# 2016_CARTE_PUISSANCEtemp.net
KiCad netlist of a schematic drawn in Altium Designer
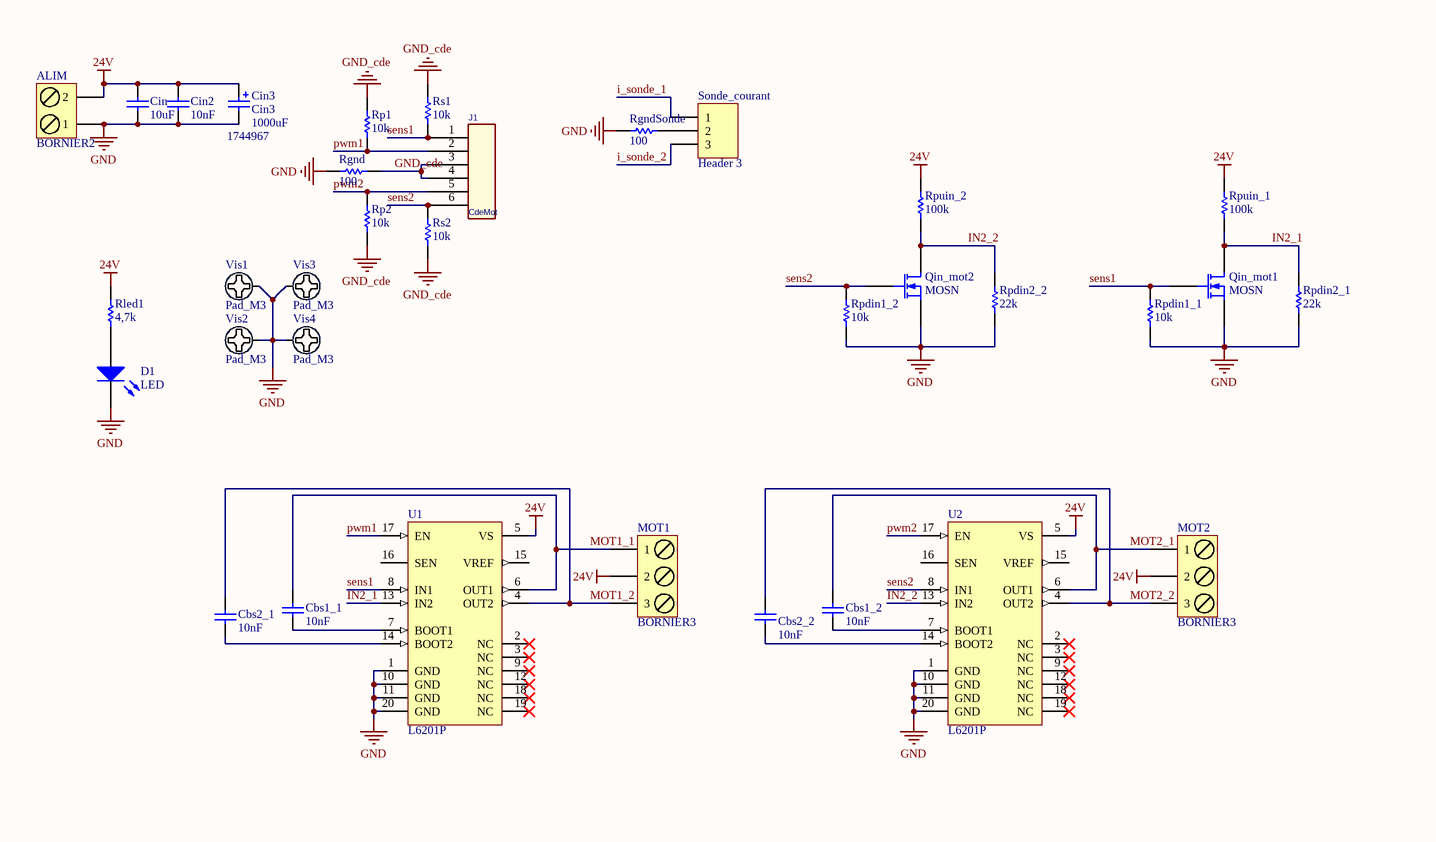
[diagram p0: 2016_CARTE_PUISSANCEtemp.SchDoc, left]
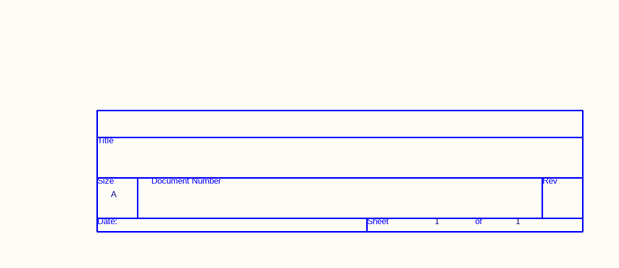
[diagram p1: 2016_CARTE_PUISSANCEtemp.SchDoc, right]

(export (version "E")
  (design (tool "Eeschema 10.0.6"))
  (components
    (comp (ref "*")
      (value "TitleBlock0")
      (fields (field (name "PAGE COUNT") "1") (field (name "PAGE NUMBER") "1") (field (name "PAGE SIZE") "A"))
      (libsource (lib "*") (part "TitleBlock0"))
    )
    (comp (ref "ALIM")
      (value "BORNIER2")
      (footprint "BORNIER2")
      (description "Terminal blocks, 2 pins, pitch=5mm")
      (libsource (lib "Robot2010") (part "BORNIER2"))
    )
    (comp (ref "Cbs1_1")
      (value "10nF")
      (footprint "C0805_N")
      (description "Capacitor")
      (fields (field (name "PUBLISHER") "Altium Limited"))
      (libsource (lib "DG_Condensateur") (part "Capacitor"))
    )
    (comp (ref "Cbs1_2")
      (value "10nF")
      (footprint "C0805_N")
      (description "Capacitor")
      (fields (field (name "PUBLISHER") "Altium Limited"))
      (libsource (lib "DG_Condensateur") (part "Capacitor"))
    )
    (comp (ref "Cbs2_1")
      (value "10nF")
      (footprint "C0805_N")
      (description "Capacitor")
      (fields (field (name "PUBLISHER") "Altium Limited"))
      (libsource (lib "DG_Condensateur") (part "Capacitor"))
    )
    (comp (ref "Cbs2_2")
      (value "10nF")
      (footprint "C0805_N")
      (description "Capacitor")
      (fields (field (name "PUBLISHER") "Altium Limited"))
      (libsource (lib "DG_Condensateur") (part "Capacitor"))
    )
    (comp (ref "Cin")
      (value "10uF")
      (footprint "C1206_N")
      (description "Capacitor")
      (fields (field (name "PUBLISHER") "Altium Limited"))
      (libsource (lib "DG_Condensateur") (part "Capacitor"))
    )
    (comp (ref "Cin2")
      (value "10nF")
      (footprint "C0805_N")
      (description "Capacitor")
      (fields (field (name "PUBLISHER") "Altium Limited"))
      (libsource (lib "DG_Condensateur") (part "Capacitor"))
    )
    (comp (ref "Cin3")
      (value "Cin3")
      (footprint "COND_POL_RAD_5.08B")
      (description "Polarized Capacitor")
      (fields
        (field (name "ALTIUM_VALUE") "1000uF")
        (field (name "FAR") "1744967")
        (field (name "PUBLISHER") "Altium Limited")
      )
      (libsource (lib "Robot2010") (part "CONDENSATEUR_POLARISE"))
    )
    (comp (ref "D1")
      (value "LED")
      (footprint "LED_3mm")
      (description "Typical LED")
      (fields (field (name "PUBLISHER") "Altium Limited"))
      (libsource (lib "DG_LED") (part "LED"))
    )
    (comp (ref "J1") (value "CdeMot") (footprint "RJ11_6/6") (libsource (lib "*") (part "CONNECTEUR_RJ12")))
    (comp (ref "MOT1")
      (value "BORNIER3")
      (footprint "BORNIER3")
      (description "Terminal blocks, 2 pins, pitch=5mm")
      (libsource (lib "Robot2010") (part "BORNIER3"))
    )
    (comp (ref "MOT2")
      (value "BORNIER3")
      (footprint "BORNIER3")
      (description "Terminal blocks, 2 pins, pitch=5mm")
      (libsource (lib "Robot2010") (part "BORNIER3"))
    )
    (comp (ref "Qin_mot1")
      (value "MOSN")
      (footprint "SOT23-3N")
      (description "N-Channel MOSFET")
      (fields (field (name "PUBLISHER") "Altium Limited"))
      (libsource (lib "_ROBOT") (part "Transistor MOSFET-N"))
    )
    (comp (ref "Qin_mot2")
      (value "MOSN")
      (footprint "SOT23-3N")
      (description "N-Channel MOSFET")
      (fields (field (name "PUBLISHER") "Altium Limited"))
      (libsource (lib "_ROBOT") (part "Transistor MOSFET-N"))
    )
    (comp (ref "Rgnd")
      (value "100")
      (footprint "R1206_N")
      (description "Resistor")
      (fields (field (name "PUBLISHER") "Altium Limited"))
      (libsource (lib "DG_Resistance") (part "Resistor"))
    )
    (comp (ref "RgndSonde")
      (value "100")
      (footprint "R1206_N")
      (description "Resistor")
      (fields (field (name "PUBLISHER") "Altium Limited"))
      (libsource (lib "DG_Resistance") (part "Resistor"))
    )
    (comp (ref "Rled1")
      (value "4,7k")
      (footprint "R1206_N")
      (description "Resistor")
      (fields (field (name "PUBLISHER") "Altium Limited"))
      (libsource (lib "DG_Resistance") (part "Resistor"))
    )
    (comp (ref "Rp1")
      (value "10k")
      (footprint "R1206_N")
      (description "Resistor")
      (fields (field (name "PUBLISHER") "Altium Limited"))
      (libsource (lib "DG_Resistance") (part "Resistor"))
    )
    (comp (ref "Rp2")
      (value "10k")
      (footprint "R1206_N")
      (description "Resistor")
      (fields (field (name "PUBLISHER") "Altium Limited"))
      (libsource (lib "DG_Resistance") (part "Resistor"))
    )
    (comp (ref "Rpdin1_1")
      (value "10k")
      (footprint "R1206_N")
      (description "Resistor")
      (fields (field (name "PUBLISHER") "Altium Limited"))
      (libsource (lib "DG_Resistance") (part "Resistor"))
    )
    (comp (ref "Rpdin1_2")
      (value "10k")
      (footprint "R1206_N")
      (description "Resistor")
      (fields (field (name "PUBLISHER") "Altium Limited"))
      (libsource (lib "DG_Resistance") (part "Resistor"))
    )
    (comp (ref "Rpdin2_1")
      (value "22k")
      (footprint "R1206_N")
      (description "Resistor")
      (fields (field (name "PUBLISHER") "Altium Limited"))
      (libsource (lib "DG_Resistance") (part "Resistor"))
    )
    (comp (ref "Rpdin2_2")
      (value "22k")
      (footprint "R1206_N")
      (description "Resistor")
      (fields (field (name "PUBLISHER") "Altium Limited"))
      (libsource (lib "DG_Resistance") (part "Resistor"))
    )
    (comp (ref "Rpuin_1")
      (value "100k")
      (footprint "R1206_N")
      (description "Resistor")
      (fields (field (name "PUBLISHER") "Altium Limited"))
      (libsource (lib "DG_Resistance") (part "Resistor"))
    )
    (comp (ref "Rpuin_2")
      (value "100k")
      (footprint "R1206_N")
      (description "Resistor")
      (fields (field (name "PUBLISHER") "Altium Limited"))
      (libsource (lib "DG_Resistance") (part "Resistor"))
    )
    (comp (ref "Rs1")
      (value "10k")
      (footprint "R1206_N")
      (description "Resistor")
      (fields (field (name "PUBLISHER") "Altium Limited"))
      (libsource (lib "DG_Resistance") (part "Resistor"))
    )
    (comp (ref "Rs2")
      (value "10k")
      (footprint "R1206_N")
      (description "Resistor")
      (fields (field (name "PUBLISHER") "Altium Limited"))
      (libsource (lib "DG_Resistance") (part "Resistor"))
    )
    (comp (ref "Sonde_courant")
      (value "Header 3")
      (footprint "HDR1X3")
      (description "Header, 3-Pin")
      (fields (field (name "PUBLISHER") "Altium Limited"))
      (libsource (lib "DG_Connecteur") (part "Header 3"))
    )
    (comp (ref "U1")
      (value "L6201P")
      (footprint "PowerSO20_N")
      (description "DMOS Full Bridge Driver")
      (fields (field (name "PUBLISHER") "Altium Limited"))
      (libsource (lib "ST Interface DC Motor Controller") (part "L6201P"))
    )
    (comp (ref "U2")
      (value "L6201P")
      (footprint "PowerSO20_N")
      (description "DMOS Full Bridge Driver")
      (fields (field (name "PUBLISHER") "Altium Limited"))
      (libsource (lib "ST Interface DC Motor Controller") (part "L6201P"))
    )
    (comp (ref "Vis1")
      (value "Pad_M3")
      (footprint "M3x6mm")
      (description "Vis M3 X 6mm _TORX_Tête 6mm")
      (fields (field (name "PUBLISHER") "Damien Guitton"))
      (libsource (lib "DG_Mecanique") (part "Vis M3 X 6mm _TORX_Tête 6mm"))
    )
    (comp (ref "Vis2")
      (value "Pad_M3")
      (footprint "M3x6mm")
      (description "Vis M3 X 6mm _TORX_Tête 6mm")
      (fields (field (name "PUBLISHER") "Damien Guitton"))
      (libsource (lib "DG_Mecanique") (part "Vis M3 X 6mm _TORX_Tête 6mm"))
    )
    (comp (ref "Vis3")
      (value "Pad_M3")
      (footprint "M3x6mm")
      (description "Vis M3 X 6mm _TORX_Tête 6mm")
      (fields (field (name "PUBLISHER") "Damien Guitton"))
      (libsource (lib "DG_Mecanique") (part "Vis M3 X 6mm _TORX_Tête 6mm"))
    )
    (comp (ref "Vis4")
      (value "Pad_M3")
      (footprint "M3x6mm")
      (description "Vis M3 X 6mm _TORX_Tête 6mm")
      (fields (field (name "PUBLISHER") "Damien Guitton"))
      (libsource (lib "DG_Mecanique") (part "Vis M3 X 6mm _TORX_Tête 6mm"))
    )
  )
  (nets
    (net (code "1") (name "/IN2_1") (class "Default")
      (node (ref "Qin_mot1") (pin "3") (pinfunction "D_3") (pintype "passive"))
      (node (ref "Rpdin2_1") (pin "2") (pinfunction "2_2") (pintype "passive"))
      (node (ref "Rpuin_1") (pin "1") (pinfunction "1_1") (pintype "passive"))
      (node (ref "U1") (pin "13") (pinfunction "IN2_13") (pintype "input"))
    )
    (net (code "2") (name "/IN2_2") (class "Default")
      (node (ref "Qin_mot2") (pin "3") (pinfunction "D_3") (pintype "passive"))
      (node (ref "Rpdin2_2") (pin "2") (pinfunction "2_2") (pintype "passive"))
      (node (ref "Rpuin_2") (pin "1") (pinfunction "1_1") (pintype "passive"))
      (node (ref "U2") (pin "13") (pinfunction "IN2_13") (pintype "input"))
    )
    (net (code "3") (name "/MOT1_1") (class "Default")
      (node (ref "Cbs1_1") (pin "2") (pinfunction "2_2") (pintype "passive"))
      (node (ref "MOT1") (pin "1") (pinfunction "1_1") (pintype "passive"))
      (node (ref "U1") (pin "6") (pinfunction "OUT1_6") (pintype "output"))
    )
    (net (code "4") (name "/MOT1_2") (class "Default")
      (node (ref "Cbs2_1") (pin "2") (pinfunction "2_2") (pintype "passive"))
      (node (ref "MOT1") (pin "3") (pinfunction "3_3") (pintype "passive"))
      (node (ref "U1") (pin "4") (pinfunction "OUT2_4") (pintype "output"))
    )
    (net (code "5") (name "/MOT2_1") (class "Default")
      (node (ref "Cbs1_2") (pin "2") (pinfunction "2_2") (pintype "passive"))
      (node (ref "MOT2") (pin "1") (pinfunction "1_1") (pintype "passive"))
      (node (ref "U2") (pin "6") (pinfunction "OUT1_6") (pintype "output"))
    )
    (net (code "6") (name "/MOT2_2") (class "Default")
      (node (ref "Cbs2_2") (pin "2") (pinfunction "2_2") (pintype "passive"))
      (node (ref "MOT2") (pin "3") (pinfunction "3_3") (pintype "passive"))
      (node (ref "U2") (pin "4") (pinfunction "OUT2_4") (pintype "output"))
    )
    (net (code "7") (name "/i_sonde_1") (class "Default")
      (node (ref "Sonde_courant") (pin "1") (pinfunction "1_1") (pintype "passive"))
    )
    (net (code "8") (name "/i_sonde_2") (class "Default")
      (node (ref "Sonde_courant") (pin "3") (pinfunction "3_3") (pintype "passive"))
    )
    (net (code "9") (name "/pwm1") (class "Default")
      (node (ref "J1") (pin "2") (pinfunction "2_2") (pintype "passive"))
      (node (ref "Rp1") (pin "1") (pinfunction "1_1") (pintype "passive"))
      (node (ref "U1") (pin "17") (pinfunction "EN_17") (pintype "input"))
    )
    (net (code "10") (name "/pwm2") (class "Default")
      (node (ref "J1") (pin "5") (pinfunction "5_5") (pintype "passive"))
      (node (ref "Rp2") (pin "2") (pinfunction "2_2") (pintype "passive"))
      (node (ref "U2") (pin "17") (pinfunction "EN_17") (pintype "input"))
    )
    (net (code "11") (name "/sens1") (class "Default")
      (node (ref "J1") (pin "1") (pinfunction "1_1") (pintype "passive"))
      (node (ref "Qin_mot1") (pin "1") (pinfunction "G_1") (pintype "passive"))
      (node (ref "Rpdin1_1") (pin "1") (pinfunction "1_1") (pintype "passive"))
      (node (ref "Rs1") (pin "1") (pinfunction "1_1") (pintype "passive"))
      (node (ref "U1") (pin "8") (pinfunction "IN1_8") (pintype "input"))
    )
    (net (code "12") (name "/sens2") (class "Default")
      (node (ref "J1") (pin "6") (pinfunction "6_6") (pintype "passive"))
      (node (ref "Qin_mot2") (pin "1") (pinfunction "G_1") (pintype "passive"))
      (node (ref "Rpdin1_2") (pin "1") (pinfunction "1_1") (pintype "passive"))
      (node (ref "Rs2") (pin "2") (pinfunction "2_2") (pintype "passive"))
      (node (ref "U2") (pin "8") (pinfunction "IN1_8") (pintype "input"))
    )
    (net (code "13") (name "24V") (class "Default")
      (node (ref "ALIM") (pin "2") (pinfunction "2_2") (pintype "passive"))
      (node (ref "Cin") (pin "2") (pinfunction "2_2") (pintype "passive"))
      (node (ref "Cin2") (pin "2") (pinfunction "2_2") (pintype "passive"))
      (node (ref "Cin3") (pin "1") (pinfunction "1_1") (pintype "passive"))
      (node (ref "MOT1") (pin "2") (pinfunction "2_2") (pintype "passive"))
      (node (ref "MOT2") (pin "2") (pinfunction "2_2") (pintype "passive"))
      (node (ref "Rled1") (pin "2") (pinfunction "2_2") (pintype "passive"))
      (node (ref "Rpuin_1") (pin "2") (pinfunction "2_2") (pintype "passive"))
      (node (ref "Rpuin_2") (pin "2") (pinfunction "2_2") (pintype "passive"))
      (node (ref "U1") (pin "5") (pinfunction "VS_5") (pintype "power_in"))
      (node (ref "U2") (pin "5") (pinfunction "VS_5") (pintype "power_in"))
    )
    (net (code "14") (name "GND") (class "Default")
      (node (ref "ALIM") (pin "1") (pinfunction "1_1") (pintype "passive"))
      (node (ref "Cin") (pin "1") (pinfunction "1_1") (pintype "passive"))
      (node (ref "Cin2") (pin "1") (pinfunction "1_1") (pintype "passive"))
      (node (ref "Cin3") (pin "2") (pinfunction "2_2") (pintype "passive"))
      (node (ref "D1") (pin "2") (pinfunction "2_2") (pintype "passive"))
      (node (ref "Qin_mot1") (pin "2") (pinfunction "S_2") (pintype "passive"))
      (node (ref "Qin_mot2") (pin "2") (pinfunction "S_2") (pintype "passive"))
      (node (ref "Rgnd") (pin "2") (pinfunction "2_2") (pintype "passive"))
      (node (ref "RgndSonde") (pin "2") (pinfunction "2_2") (pintype "passive"))
      (node (ref "Rpdin1_1") (pin "2") (pinfunction "2_2") (pintype "passive"))
      (node (ref "Rpdin1_2") (pin "2") (pinfunction "2_2") (pintype "passive"))
      (node (ref "Rpdin2_1") (pin "1") (pinfunction "1_1") (pintype "passive"))
      (node (ref "Rpdin2_2") (pin "1") (pinfunction "1_1") (pintype "passive"))
      (node (ref "U1") (pin "1") (pinfunction "GND_1") (pintype "power_in"))
      (node (ref "U1") (pin "10") (pinfunction "GND_10") (pintype "power_in"))
      (node (ref "U1") (pin "11") (pinfunction "GND_11") (pintype "power_in"))
      (node (ref "U1") (pin "20") (pinfunction "GND_20") (pintype "power_in"))
      (node (ref "U2") (pin "1") (pinfunction "GND_1") (pintype "power_in"))
      (node (ref "U2") (pin "10") (pinfunction "GND_10") (pintype "power_in"))
      (node (ref "U2") (pin "11") (pinfunction "GND_11") (pintype "power_in"))
      (node (ref "U2") (pin "20") (pinfunction "GND_20") (pintype "power_in"))
      (node (ref "Vis1") (pin "1") (pinfunction "1_1") (pintype "passive"))
      (node (ref "Vis2") (pin "1") (pinfunction "1_1") (pintype "passive"))
      (node (ref "Vis3") (pin "1") (pinfunction "1_1") (pintype "passive"))
      (node (ref "Vis4") (pin "1") (pinfunction "1_1") (pintype "passive"))
    )
    (net (code "15") (name "GND_cde") (class "Default")
      (node (ref "J1") (pin "3") (pinfunction "3_3") (pintype "passive"))
      (node (ref "J1") (pin "4") (pinfunction "4_4") (pintype "passive"))
      (node (ref "Rgnd") (pin "1") (pinfunction "1_1") (pintype "passive"))
      (node (ref "Rp1") (pin "2") (pinfunction "2_2") (pintype "passive"))
      (node (ref "Rp2") (pin "1") (pinfunction "1_1") (pintype "passive"))
      (node (ref "Rs1") (pin "2") (pinfunction "2_2") (pintype "passive"))
      (node (ref "Rs2") (pin "1") (pinfunction "1_1") (pintype "passive"))
    )
    (net (code "16") (name "Net-(D1-Pad1)") (class "Default")
      (node (ref "D1") (pin "1") (pinfunction "1_1") (pintype "passive"))
      (node (ref "Rled1") (pin "1") (pinfunction "1_1") (pintype "passive"))
    )
    (net (code "17") (name "Net-(RgndSonde-Pad1)") (class "Default")
      (node (ref "RgndSonde") (pin "1") (pinfunction "1_1") (pintype "passive"))
      (node (ref "Sonde_courant") (pin "2") (pinfunction "2_2") (pintype "passive"))
    )
    (net (code "18") (name "Net-(U1-BOOT1)") (class "Default")
      (node (ref "Cbs1_1") (pin "1") (pinfunction "1_1") (pintype "passive"))
      (node (ref "U1") (pin "7") (pinfunction "BOOT1_7") (pintype "input"))
    )
    (net (code "19") (name "Net-(U1-BOOT2)") (class "Default")
      (node (ref "Cbs2_1") (pin "1") (pinfunction "1_1") (pintype "passive"))
      (node (ref "U1") (pin "14") (pinfunction "BOOT2_14") (pintype "input"))
    )
    (net (code "20") (name "Net-(U2-BOOT1)") (class "Default")
      (node (ref "Cbs1_2") (pin "1") (pinfunction "1_1") (pintype "passive"))
      (node (ref "U2") (pin "7") (pinfunction "BOOT1_7") (pintype "input"))
    )
    (net (code "21") (name "Net-(U2-BOOT2)") (class "Default")
      (node (ref "Cbs2_2") (pin "1") (pinfunction "1_1") (pintype "passive"))
      (node (ref "U2") (pin "14") (pinfunction "BOOT2_14") (pintype "input"))
    )
    (net (code "22") (name "unconnected-(U1-NC-Pad2)") (class "Default")
      (node (ref "U1") (pin "2") (pinfunction "NC_2") (pintype "passive+no_connect"))
    )
    (net (code "23") (name "unconnected-(U1-NC-Pad3)") (class "Default")
      (node (ref "U1") (pin "3") (pinfunction "NC_3") (pintype "passive+no_connect"))
    )
    (net (code "24") (name "unconnected-(U1-NC-Pad9)") (class "Default")
      (node (ref "U1") (pin "9") (pinfunction "NC_9") (pintype "passive+no_connect"))
    )
    (net (code "25") (name "unconnected-(U1-NC-Pad12)") (class "Default")
      (node (ref "U1") (pin "12") (pinfunction "NC_12") (pintype "passive+no_connect"))
    )
    (net (code "26") (name "unconnected-(U1-NC-Pad18)") (class "Default")
      (node (ref "U1") (pin "18") (pinfunction "NC_18") (pintype "passive+no_connect"))
    )
    (net (code "27") (name "unconnected-(U1-NC-Pad19)") (class "Default")
      (node (ref "U1") (pin "19") (pinfunction "NC_19") (pintype "passive+no_connect"))
    )
    (net (code "28") (name "unconnected-(U1-SEN-Pad16)") (class "Default")
      (node (ref "U1") (pin "16") (pinfunction "SEN_16") (pintype "passive"))
    )
    (net (code "29") (name "unconnected-(U1-VREF-Pad15)") (class "Default")
      (node (ref "U1") (pin "15") (pinfunction "VREF_15") (pintype "output"))
    )
    (net (code "30") (name "unconnected-(U2-NC-Pad2)") (class "Default")
      (node (ref "U2") (pin "2") (pinfunction "NC_2") (pintype "passive+no_connect"))
    )
    (net (code "31") (name "unconnected-(U2-NC-Pad3)") (class "Default")
      (node (ref "U2") (pin "3") (pinfunction "NC_3") (pintype "passive+no_connect"))
    )
    (net (code "32") (name "unconnected-(U2-NC-Pad9)") (class "Default")
      (node (ref "U2") (pin "9") (pinfunction "NC_9") (pintype "passive+no_connect"))
    )
    (net (code "33") (name "unconnected-(U2-NC-Pad12)") (class "Default")
      (node (ref "U2") (pin "12") (pinfunction "NC_12") (pintype "passive+no_connect"))
    )
    (net (code "34") (name "unconnected-(U2-NC-Pad18)") (class "Default")
      (node (ref "U2") (pin "18") (pinfunction "NC_18") (pintype "passive+no_connect"))
    )
    (net (code "35") (name "unconnected-(U2-NC-Pad19)") (class "Default")
      (node (ref "U2") (pin "19") (pinfunction "NC_19") (pintype "passive+no_connect"))
    )
    (net (code "36") (name "unconnected-(U2-SEN-Pad16)") (class "Default")
      (node (ref "U2") (pin "16") (pinfunction "SEN_16") (pintype "passive"))
    )
    (net (code "37") (name "unconnected-(U2-VREF-Pad15)") (class "Default")
      (node (ref "U2") (pin "15") (pinfunction "VREF_15") (pintype "output"))
    )
  )
)
